# Solar_ve_r_zgar_kart.net
KiCad netlist of a schematic drawn in EAGLE
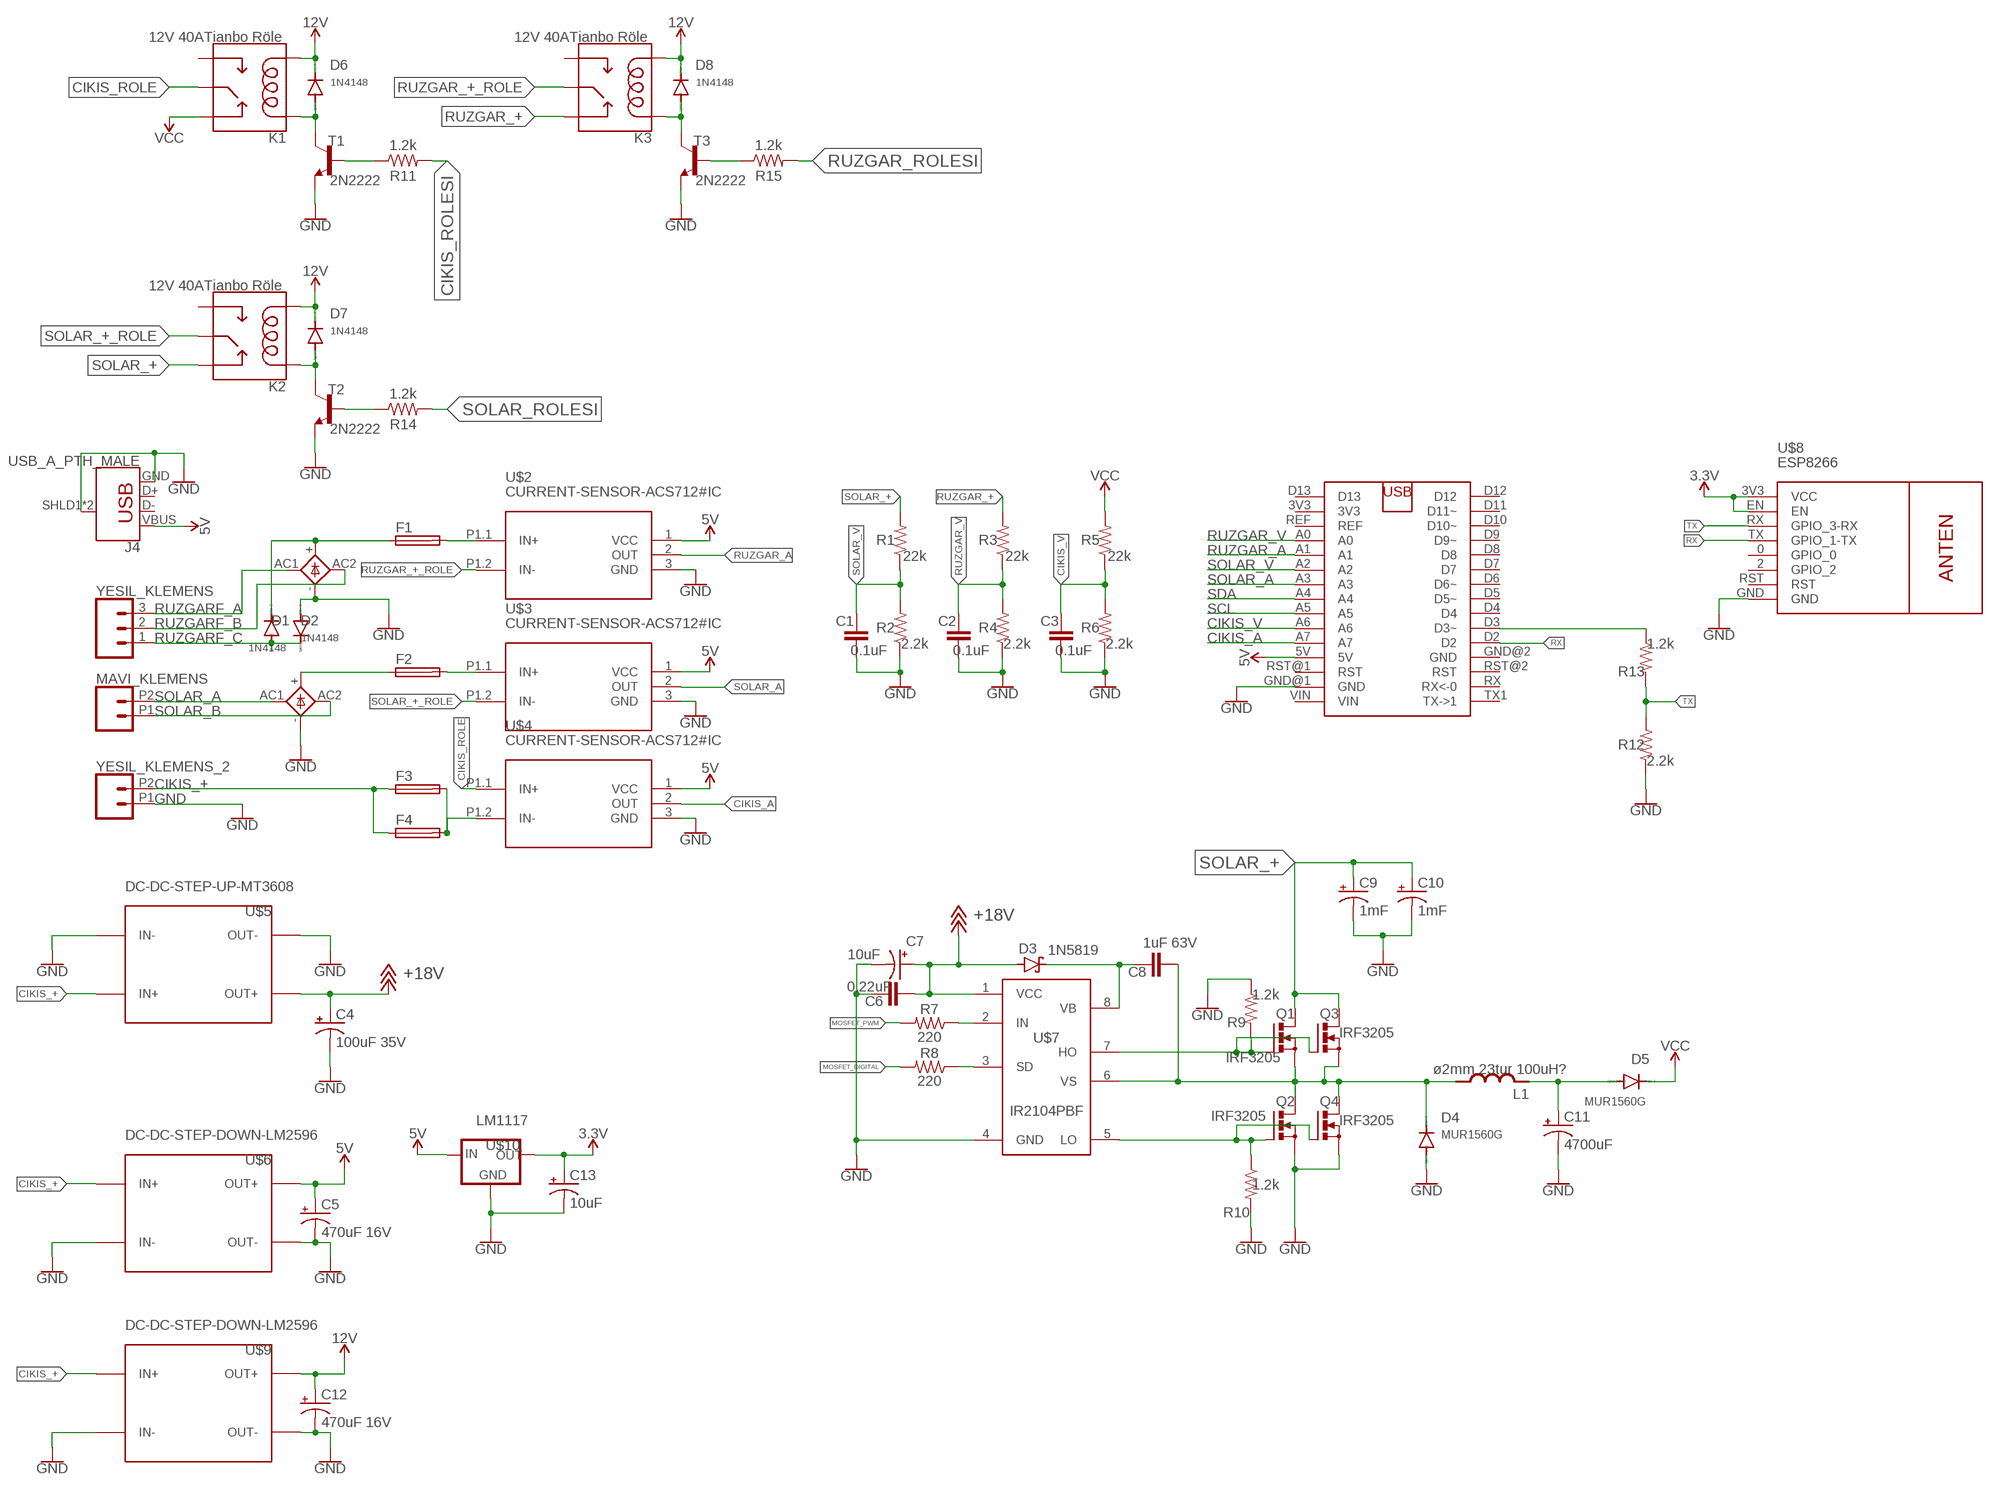
[diagram p0: schematic, sheet 1]

(export (version "E")
  (design (tool "Eeschema 10.0.6"))
  (components
    (comp (ref "B1")
      (value "FB15")
      (footprint "eagle-import:FB15")
      (libsource (lib "eagle-import") (part "FB15"))
    )
    (comp (ref "B2")
      (value "FB15")
      (footprint "eagle-import:FB15")
      (libsource (lib "eagle-import") (part "FB15"))
    )
    (comp (ref "C1")
      (value "0.1uF")
      (footprint "eagle-import:CAP-PTH-SMALL-KIT")
      (libsource (lib "eagle-import") (part "0.1UF-KIT-EZ-50V-20%"))
    )
    (comp (ref "C2")
      (value "0.1uF")
      (footprint "eagle-import:CAP-PTH-SMALL-KIT")
      (libsource (lib "eagle-import") (part "0.1UF-KIT-EZ-50V-20%"))
    )
    (comp (ref "C3")
      (value "0.1uF")
      (footprint "eagle-import:CAP-PTH-SMALL-KIT")
      (libsource (lib "eagle-import") (part "0.1UF-KIT-EZ-50V-20%"))
    )
    (comp (ref "C4")
      (value "100uF 35V")
      (footprint "eagle-import:CPOL-RADIAL-2.5MM-6.5MM")
      (libsource (lib "eagle-import") (part "100UF-POLAR-RADIAL-2.5MM-25V-20%"))
    )
    (comp (ref "C5")
      (value "470uF 16V")
      (footprint "eagle-import:CPOL-RADIAL-2.5MM-6.5MM")
      (libsource (lib "eagle-import") (part "100UF-POLAR-RADIAL-2.5MM-25V-20%"))
    )
    (comp (ref "C6")
      (value "0.22uF")
      (footprint "eagle-import:CAP-PTH-SMALL-KIT")
      (libsource (lib "eagle-import") (part "0.1UF-KIT-EZ-50V-20%"))
    )
    (comp (ref "C7")
      (value "10uF")
      (footprint "eagle-import:CPOL-RADIAL-2.5MM-5MM")
      (libsource (lib "eagle-import") (part "10UF-POLAR-RADIAL-2.5MM-25V-20%"))
    )
    (comp (ref "C8")
      (value "1uF 63V")
      (footprint "eagle-import:CAP-PTH-SMALL-KIT")
      (libsource (lib "eagle-import") (part "0.1UF-KIT-EZ-50V-20%"))
    )
    (comp (ref "C9")
      (value "1mF")
      (footprint "eagle-import:CPOL-RADIAL-5MM-10MM")
      (libsource (lib "eagle-import") (part "1000UF-RADIAL-5MM-25V-20%"))
    )
    (comp (ref "C10")
      (value "1mF")
      (footprint "eagle-import:CPOL-RADIAL-5MM-10MM")
      (libsource (lib "eagle-import") (part "1000UF-RADIAL-5MM-25V-20%"))
    )
    (comp (ref "C11")
      (value "4700uF")
      (footprint "eagle-import:CPOL-RADIAL-5MM-10MM")
      (libsource (lib "eagle-import") (part "1000UF-RADIAL-5MM-25V-20%"))
    )
    (comp (ref "C12")
      (value "470uF 16V")
      (footprint "eagle-import:CPOL-RADIAL-2.5MM-6.5MM")
      (libsource (lib "eagle-import") (part "100UF-POLAR-RADIAL-2.5MM-25V-20%"))
    )
    (comp (ref "C13")
      (value "10uF")
      (footprint "eagle-import:CPOL-RADIAL-2.5MM-5MM")
      (libsource (lib "eagle-import") (part "10UF-POLAR-RADIAL-2.5MM-25V-20%"))
    )
    (comp (ref "D1")
      (value "1N4148")
      (footprint "eagle-import:DO35-7")
      (libsource (lib "eagle-import") (part "1N4148DO35-7"))
    )
    (comp (ref "D2")
      (value "1N4148")
      (footprint "eagle-import:DO35-7")
      (libsource (lib "eagle-import") (part "1N4148DO35-7"))
    )
    (comp (ref "D3")
      (value "1N5819")
      (footprint "eagle-import:DO41-7.6")
      (libsource (lib "eagle-import") (part "1N5819-B"))
    )
    (comp (ref "D4")
      (value "MUR1560G")
      (footprint "eagle-import:TO220ACS")
      (libsource (lib "eagle-import") (part "DIODE-TO220V"))
    )
    (comp (ref "D5")
      (value "MUR1560G")
      (footprint "eagle-import:TO220ACS")
      (libsource (lib "eagle-import") (part "DIODE-TO220V"))
    )
    (comp (ref "D6")
      (value "1N4148")
      (footprint "eagle-import:DO35-7")
      (libsource (lib "eagle-import") (part "1N4148DO35-7"))
    )
    (comp (ref "D7")
      (value "1N4148")
      (footprint "eagle-import:DO35-7")
      (libsource (lib "eagle-import") (part "1N4148DO35-7"))
    )
    (comp (ref "D8")
      (value "1N4148")
      (footprint "eagle-import:DO35-7")
      (libsource (lib "eagle-import") (part "1N4148DO35-7"))
    )
    (comp (ref "F1")
      (value "19560")
      (footprint "eagle-import:19560")
      (fields (field (name "MPN") "56000001009"))
      (libsource (lib "eagle-import") (part "19560"))
    )
    (comp (ref "F2")
      (value "19560")
      (footprint "eagle-import:19560")
      (fields (field (name "MPN") "56000001009"))
      (libsource (lib "eagle-import") (part "19560"))
    )
    (comp (ref "F3")
      (value "19560")
      (footprint "eagle-import:19560")
      (fields (field (name "MPN") "56000001009"))
      (libsource (lib "eagle-import") (part "19560"))
    )
    (comp (ref "F4")
      (value "19560")
      (footprint "eagle-import:19560")
      (fields (field (name "MPN") "56000001009"))
      (libsource (lib "eagle-import") (part "19560"))
    )
    (comp (ref "J4")
      (value "USB_A_PTH_MALE")
      (footprint "eagle-import:USB-A-H")
      (libsource (lib "eagle-import") (part "USB_A_PTH_MALE"))
    )
    (comp (ref "K1")
      (value "12V 40ATianbo Röle")
      (footprint "eagle-import:RELAY-JZC")
      (libsource (lib "eagle-import") (part "RELAY-SPDT-JZC-11F"))
    )
    (comp (ref "K2")
      (value "12V 40ATianbo Röle")
      (footprint "eagle-import:RELAY-JZC")
      (libsource (lib "eagle-import") (part "RELAY-SPDT-JZC-11F"))
    )
    (comp (ref "K3")
      (value "12V 40ATianbo Röle")
      (footprint "eagle-import:RELAY-JZC")
      (libsource (lib "eagle-import") (part "RELAY-SPDT-JZC-11F"))
    )
    (comp (ref "L1")
      (value "ø2mm 23tur 100uH?")
      (footprint "eagle-import:L10-2")
      (libsource (lib "eagle-import") (part "L10-2"))
    )
    (comp (ref "MAVI_KLEMENS")
      (value "CONN_022.54MM_SCREWTERM")
      (footprint "eagle-import:1X02_2.54_SCREWTERM")
      (libsource (lib "eagle-import") (part "CONN_022.54MM_SCREWTERM"))
    )
    (comp (ref "Q1")
      (value "IRF3205")
      (footprint "eagle-import:TO220BV")
      (libsource (lib "eagle-import") (part "PMOSFET_NTO220BV"))
    )
    (comp (ref "Q2")
      (value "IRF3205")
      (footprint "eagle-import:TO220BV")
      (libsource (lib "eagle-import") (part "PMOSFET_NTO220BV"))
    )
    (comp (ref "Q3")
      (value "IRF3205")
      (footprint "eagle-import:TO220BV")
      (libsource (lib "eagle-import") (part "PMOSFET_NTO220BV"))
    )
    (comp (ref "Q4")
      (value "IRF3205")
      (footprint "eagle-import:TO220BV")
      (libsource (lib "eagle-import") (part "PMOSFET_NTO220BV"))
    )
    (comp (ref "R1")
      (value "22k")
      (footprint "eagle-import:AXIAL-0.3")
      (libsource (lib "eagle-import") (part "RESISTORAXIAL-0.3"))
    )
    (comp (ref "R2")
      (value "2.2k")
      (footprint "eagle-import:AXIAL-0.3")
      (libsource (lib "eagle-import") (part "RESISTORAXIAL-0.3"))
    )
    (comp (ref "R3")
      (value "22k")
      (footprint "eagle-import:AXIAL-0.3")
      (libsource (lib "eagle-import") (part "RESISTORAXIAL-0.3"))
    )
    (comp (ref "R4")
      (value "2.2k")
      (footprint "eagle-import:AXIAL-0.3")
      (libsource (lib "eagle-import") (part "RESISTORAXIAL-0.3"))
    )
    (comp (ref "R5")
      (value "22k")
      (footprint "eagle-import:AXIAL-0.3")
      (libsource (lib "eagle-import") (part "RESISTORAXIAL-0.3"))
    )
    (comp (ref "R6")
      (value "2.2k")
      (footprint "eagle-import:AXIAL-0.3")
      (libsource (lib "eagle-import") (part "RESISTORAXIAL-0.3"))
    )
    (comp (ref "R7")
      (value "220")
      (footprint "eagle-import:AXIAL-0.3")
      (libsource (lib "eagle-import") (part "RESISTORAXIAL-0.3"))
    )
    (comp (ref "R8")
      (value "220")
      (footprint "eagle-import:AXIAL-0.3")
      (libsource (lib "eagle-import") (part "RESISTORAXIAL-0.3"))
    )
    (comp (ref "R9")
      (value "1.2k")
      (footprint "eagle-import:AXIAL-0.3")
      (libsource (lib "eagle-import") (part "RESISTORAXIAL-0.3"))
    )
    (comp (ref "R10")
      (value "1.2k")
      (footprint "eagle-import:AXIAL-0.3")
      (libsource (lib "eagle-import") (part "RESISTORAXIAL-0.3"))
    )
    (comp (ref "R11")
      (value "1.2k")
      (footprint "eagle-import:AXIAL-0.3")
      (libsource (lib "eagle-import") (part "RESISTORAXIAL-0.3"))
    )
    (comp (ref "R12")
      (value "2.2k")
      (footprint "eagle-import:AXIAL-0.3")
      (libsource (lib "eagle-import") (part "RESISTORAXIAL-0.3"))
    )
    (comp (ref "R13")
      (value "1.2k")
      (footprint "eagle-import:AXIAL-0.3")
      (libsource (lib "eagle-import") (part "RESISTORAXIAL-0.3"))
    )
    (comp (ref "R14")
      (value "1.2k")
      (footprint "eagle-import:AXIAL-0.3")
      (libsource (lib "eagle-import") (part "RESISTORAXIAL-0.3"))
    )
    (comp (ref "R15")
      (value "1.2k")
      (footprint "eagle-import:AXIAL-0.3")
      (libsource (lib "eagle-import") (part "RESISTORAXIAL-0.3"))
    )
    (comp (ref "T1")
      (value "2N2222")
      (footprint "eagle-import:TO92-EBC")
      (libsource (lib "eagle-import") (part "-NPN-TO92-EBC2N2222"))
    )
    (comp (ref "T2")
      (value "2N2222")
      (footprint "eagle-import:TO92-EBC")
      (libsource (lib "eagle-import") (part "-NPN-TO92-EBC2N2222"))
    )
    (comp (ref "T3")
      (value "2N2222")
      (footprint "eagle-import:TO92-EBC")
      (libsource (lib "eagle-import") (part "-NPN-TO92-EBC2N2222"))
    )
    (comp (ref "U$1")
      (value "ARDUINO_NANO")
      (footprint "eagle-import:ARDUINO_NANO")
      (libsource (lib "eagle-import") (part "ARDUINO_NANO"))
    )
    (comp (ref "U$2")
      (value "CURRENT-SENSOR-ACS712#IC")
      (footprint "eagle-import:CURRENT-SENSOR-ACS712#IC")
      (libsource (lib "eagle-import") (part "CURRENT-SENSOR-ACS712#IC"))
    )
    (comp (ref "U$3")
      (value "CURRENT-SENSOR-ACS712#IC")
      (footprint "eagle-import:CURRENT-SENSOR-ACS712#IC")
      (libsource (lib "eagle-import") (part "CURRENT-SENSOR-ACS712#IC"))
    )
    (comp (ref "U$4")
      (value "CURRENT-SENSOR-ACS712#IC")
      (footprint "eagle-import:CURRENT-SENSOR-ACS712#IC")
      (libsource (lib "eagle-import") (part "CURRENT-SENSOR-ACS712#IC"))
    )
    (comp (ref "U$5")
      (value "DC-DC-STEP-UP-MT3608")
      (footprint "eagle-import:DC-DC-STEP-UP-MT3608")
      (fields (field (name "SPICEPREFIX") "E"))
      (libsource (lib "eagle-import") (part "DC-DC-STEP-UP-MT3608"))
    )
    (comp (ref "U$6")
      (value "DC-DC-STEP-DOWN-LM2596")
      (footprint "eagle-import:DC-DC-STEP-DOWN-LM2596")
      (libsource (lib "eagle-import") (part "DC-DC-STEP-DOWN-LM2596"))
    )
    (comp (ref "U$7")
      (value "IR2104PBF")
      (footprint "eagle-import:DIP-8")
      (libsource (lib "eagle-import") (part "IR2104PBF"))
    )
    (comp (ref "U$8")
      (value "ESP8266")
      (footprint "eagle-import:ESP8266")
      (libsource (lib "eagle-import") (part "ESP8266"))
    )
    (comp (ref "U$9")
      (value "DC-DC-STEP-DOWN-LM2596")
      (footprint "eagle-import:DC-DC-STEP-DOWN-LM2596")
      (libsource (lib "eagle-import") (part "DC-DC-STEP-DOWN-LM2596"))
    )
    (comp (ref "U$10")
      (value "LM1117")
      (footprint "eagle-import:TO-220")
      (libsource (lib "eagle-import") (part "LM1117"))
    )
    (comp (ref "YESIL_KLEMENS")
      (value "CONN_03-SCREW-5MM")
      (footprint "eagle-import:SCREWTERMINAL-5MM-3")
      (libsource (lib "eagle-import") (part "CONN_03-SCREW-5MM"))
    )
    (comp (ref "YESIL_KLEMENS_2")
      (value "CONN_022.54MM_SCREWTERM")
      (footprint "eagle-import:1X02_2.54_SCREWTERM")
      (libsource (lib "eagle-import") (part "CONN_022.54MM_SCREWTERM"))
    )
  )
  (nets
    (net (code "1") (name "+18V") (class "Default")
      (node (ref "C4") (pin "1") (pinfunction "+_1") (pintype "passive"))
      (node (ref "C6") (pin "2") (pinfunction "2_2") (pintype "passive"))
      (node (ref "C7") (pin "1") (pinfunction "+_1") (pintype "passive"))
      (node (ref "D3") (pin "A") (pinfunction "A_A") (pintype "passive"))
      (node (ref "U$5") (pin "OUT+") (pinfunction "OUT+_OUT+") (pintype "bidirectional"))
      (node (ref "U$7") (pin "1") (pinfunction "VCC_1") (pintype "bidirectional"))
    )
    (net (code "2") (name "/RUZGARF_A") (class "Default")
      (node (ref "B2") (pin "AC1") (pinfunction "AC1_AC1") (pintype "passive"))
      (node (ref "YESIL_KLEMENS") (pin "3") (pinfunction "3_3") (pintype "passive"))
    )
    (net (code "3") (name "/RUZGARF_B") (class "Default")
      (node (ref "B2") (pin "AC2") (pinfunction "AC2_AC2") (pintype "passive"))
      (node (ref "YESIL_KLEMENS") (pin "2") (pinfunction "2_2") (pintype "passive"))
    )
    (net (code "4") (name "/RUZGARF_C") (class "Default")
      (node (ref "D1") (pin "A") (pinfunction "A_A") (pintype "passive"))
      (node (ref "D2") (pin "C") (pinfunction "C_C") (pintype "passive"))
      (node (ref "YESIL_KLEMENS") (pin "1") (pinfunction "1_1") (pintype "passive"))
    )
    (net (code "5") (name "/SCL") (class "Default")
      (node (ref "U$1") (pin "A5") (pinfunction "A5_A5") (pintype "bidirectional"))
    )
    (net (code "6") (name "/SDA") (class "Default")
      (node (ref "U$1") (pin "A4") (pinfunction "A4_A4") (pintype "bidirectional"))
    )
    (net (code "7") (name "/SOLAR_B") (class "Default")
      (node (ref "B1") (pin "AC2") (pinfunction "AC2_AC2") (pintype "passive"))
      (node (ref "MAVI_KLEMENS") (pin "P1") (pinfunction "1_P1") (pintype "passive"))
    )
    (net (code "8") (name "3.3V") (class "Default")
      (node (ref "C13") (pin "1") (pinfunction "+_1") (pintype "passive"))
      (node (ref "U$10") (pin "2") (pinfunction "OUT_2") (pintype "output"))
      (node (ref "U$8") (pin "3V3") (pinfunction "VCC_3V3") (pintype "power_in"))
      (node (ref "U$8") (pin "EN") (pinfunction "EN_EN") (pintype "bidirectional"))
    )
    (net (code "9") (name "5V") (class "Default")
      (node (ref "C5") (pin "1") (pinfunction "+_1") (pintype "passive"))
      (node (ref "J4") (pin "VBUS") (pinfunction "VBUS_VBUS") (pintype "power_in"))
      (node (ref "U$1") (pin "5V") (pinfunction "5V_5V") (pintype "bidirectional"))
      (node (ref "U$10") (pin "3") (pinfunction "IN_3") (pintype "input"))
      (node (ref "U$2") (pin "1") (pinfunction "VCC_1") (pintype "power_in"))
      (node (ref "U$3") (pin "1") (pinfunction "VCC_1") (pintype "power_in"))
      (node (ref "U$4") (pin "1") (pinfunction "VCC_1") (pintype "power_in"))
      (node (ref "U$6") (pin "OUT+") (pinfunction "OUT+_OUT+") (pintype "bidirectional"))
    )
    (net (code "10") (name "12V") (class "Default")
      (node (ref "C12") (pin "1") (pinfunction "+_1") (pintype "passive"))
      (node (ref "D6") (pin "C") (pinfunction "C_C") (pintype "passive"))
      (node (ref "D7") (pin "C") (pinfunction "C_C") (pintype "passive"))
      (node (ref "D8") (pin "C") (pinfunction "C_C") (pintype "passive"))
      (node (ref "K1") (pin "1") (pinfunction "COIL2_1") (pintype "bidirectional"))
      (node (ref "K2") (pin "1") (pinfunction "COIL2_1") (pintype "bidirectional"))
      (node (ref "K3") (pin "1") (pinfunction "COIL2_1") (pintype "bidirectional"))
      (node (ref "U$9") (pin "OUT+") (pinfunction "OUT+_OUT+") (pintype "bidirectional"))
    )
    (net (code "11") (name "CIKIS_+") (class "Default")
      (node (ref "F3") (pin "1") (pinfunction "1_1") (pintype "passive"))
      (node (ref "F4") (pin "1") (pinfunction "1_1") (pintype "passive"))
      (node (ref "U$5") (pin "IN+") (pinfunction "IN+_IN+") (pintype "bidirectional"))
      (node (ref "U$6") (pin "IN+") (pinfunction "IN+_IN+") (pintype "bidirectional"))
      (node (ref "U$9") (pin "IN+") (pinfunction "IN+_IN+") (pintype "bidirectional"))
      (node (ref "YESIL_KLEMENS_2") (pin "P2") (pinfunction "2_P2") (pintype "passive"))
    )
    (net (code "12") (name "CIKIS_A") (class "Default")
      (node (ref "U$1") (pin "A7") (pinfunction "A7_A7") (pintype "bidirectional"))
      (node (ref "U$4") (pin "2") (pinfunction "OUT_2") (pintype "output"))
    )
    (net (code "13") (name "CIKIS_ROLE") (class "Default")
      (node (ref "K1") (pin "4") (pinfunction "MAIN_4") (pintype "bidirectional"))
      (node (ref "U$4") (pin "P1.1") (pinfunction "IN+_P1.1") (pintype "bidirectional"))
    )
    (net (code "14") (name "CIKIS_ROLESI") (class "Default")
      (node (ref "R11") (pin "P$2") (pinfunction "2_P$2") (pintype "passive"))
    )
    (net (code "15") (name "CIKIS_V") (class "Default")
      (node (ref "C3") (pin "1") (pinfunction "1_1") (pintype "passive"))
      (node (ref "R5") (pin "P$1") (pinfunction "1_P$1") (pintype "passive"))
      (node (ref "R6") (pin "P$2") (pinfunction "2_P$2") (pintype "passive"))
      (node (ref "U$1") (pin "A6") (pinfunction "A6_A6") (pintype "bidirectional"))
    )
    (net (code "16") (name "GND") (class "Default")
      (node (ref "B1") (pin "-") (pinfunction "-_-") (pintype "passive"))
      (node (ref "B2") (pin "-") (pinfunction "-_-") (pintype "passive"))
      (node (ref "C1") (pin "2") (pinfunction "2_2") (pintype "passive"))
      (node (ref "C10") (pin "-") (pinfunction "-_-") (pintype "passive"))
      (node (ref "C11") (pin "-") (pinfunction "-_-") (pintype "passive"))
      (node (ref "C12") (pin "2") (pinfunction "-_2") (pintype "passive"))
      (node (ref "C13") (pin "2") (pinfunction "-_2") (pintype "passive"))
      (node (ref "C2") (pin "2") (pinfunction "2_2") (pintype "passive"))
      (node (ref "C3") (pin "2") (pinfunction "2_2") (pintype "passive"))
      (node (ref "C4") (pin "2") (pinfunction "-_2") (pintype "passive"))
      (node (ref "C5") (pin "2") (pinfunction "-_2") (pintype "passive"))
      (node (ref "C6") (pin "1") (pinfunction "1_1") (pintype "passive"))
      (node (ref "C7") (pin "2") (pinfunction "-_2") (pintype "passive"))
      (node (ref "C9") (pin "-") (pinfunction "-_-") (pintype "passive"))
      (node (ref "D2") (pin "A") (pinfunction "A_A") (pintype "passive"))
      (node (ref "D4") (pin "A") (pinfunction "A_A") (pintype "passive"))
      (node (ref "J4") (pin "GND") (pinfunction "GND_GND") (pintype "power_in"))
      (node (ref "J4") (pin "SHLD1") (pinfunction "SHIELD_SHLD1") (pintype "bidirectional"))
      (node (ref "J4") (pin "SHLD2") (pinfunction "SHIELD_SHLD2") (pintype "bidirectional"))
      (node (ref "Q2") (pin "S") (pinfunction "S_S") (pintype "passive"))
      (node (ref "Q4") (pin "S") (pinfunction "S_S") (pintype "passive"))
      (node (ref "R10") (pin "P$2") (pinfunction "2_P$2") (pintype "passive"))
      (node (ref "R12") (pin "P$1") (pinfunction "1_P$1") (pintype "passive"))
      (node (ref "R2") (pin "P$1") (pinfunction "1_P$1") (pintype "passive"))
      (node (ref "R4") (pin "P$1") (pinfunction "1_P$1") (pintype "passive"))
      (node (ref "R6") (pin "P$1") (pinfunction "1_P$1") (pintype "passive"))
      (node (ref "R9") (pin "P$1") (pinfunction "1_P$1") (pintype "passive"))
      (node (ref "T1") (pin "E") (pinfunction "E_E") (pintype "passive"))
      (node (ref "T2") (pin "E") (pinfunction "E_E") (pintype "passive"))
      (node (ref "T3") (pin "E") (pinfunction "E_E") (pintype "passive"))
      (node (ref "U$1") (pin "GND@1") (pinfunction "GND_GND@1") (pintype "bidirectional"))
      (node (ref "U$10") (pin "1") (pinfunction "GND_1") (pintype "input"))
      (node (ref "U$2") (pin "3") (pinfunction "GND_3") (pintype "power_in"))
      (node (ref "U$3") (pin "3") (pinfunction "GND_3") (pintype "power_in"))
      (node (ref "U$4") (pin "3") (pinfunction "GND_3") (pintype "power_in"))
      (node (ref "U$5") (pin "IN-") (pinfunction "IN-_IN-") (pintype "bidirectional"))
      (node (ref "U$5") (pin "OUT-") (pinfunction "OUT-_OUT-") (pintype "bidirectional"))
      (node (ref "U$6") (pin "IN-") (pinfunction "IN-_IN-") (pintype "bidirectional"))
      (node (ref "U$6") (pin "OUT-") (pinfunction "OUT-_OUT-") (pintype "bidirectional"))
      (node (ref "U$7") (pin "4") (pinfunction "GND_4") (pintype "bidirectional"))
      (node (ref "U$8") (pin "GND") (pinfunction "GND_GND") (pintype "power_in"))
      (node (ref "U$9") (pin "IN-") (pinfunction "IN-_IN-") (pintype "bidirectional"))
      (node (ref "U$9") (pin "OUT-") (pinfunction "OUT-_OUT-") (pintype "bidirectional"))
      (node (ref "YESIL_KLEMENS_2") (pin "P1") (pinfunction "1_P1") (pintype "passive"))
    )
    (net (code "17") (name "MOSFET_DIGITAL") (class "Default")
      (node (ref "R8") (pin "P$2") (pinfunction "2_P$2") (pintype "passive"))
    )
    (net (code "18") (name "MOSFET_PWM") (class "Default")
      (node (ref "R7") (pin "P$2") (pinfunction "2_P$2") (pintype "passive"))
    )
    (net (code "19") (name "Net-(B1-Pad+)") (class "Default")
      (node (ref "B1") (pin "+") (pinfunction "+_+") (pintype "passive"))
      (node (ref "F2") (pin "1") (pinfunction "1_1") (pintype "passive"))
    )
    (net (code "20") (name "Net-(B2-Pad+)") (class "Default")
      (node (ref "B2") (pin "+") (pinfunction "+_+") (pintype "passive"))
      (node (ref "D1") (pin "C") (pinfunction "C_C") (pintype "passive"))
      (node (ref "F1") (pin "1") (pinfunction "1_1") (pintype "passive"))
    )
    (net (code "21") (name "Net-(C11-Pad+)") (class "Default")
      (node (ref "C11") (pin "+") (pinfunction "+_+") (pintype "passive"))
      (node (ref "D5") (pin "A") (pinfunction "A_A") (pintype "passive"))
      (node (ref "L1") (pin "P$3") (pinfunction "2_P$3") (pintype "passive"))
      (node (ref "L1") (pin "P$4") (pinfunction "2_P$4") (pintype "passive"))
    )
    (net (code "22") (name "Net-(K1-COIL1)") (class "Default")
      (node (ref "D6") (pin "A") (pinfunction "A_A") (pintype "passive"))
      (node (ref "K1") (pin "5") (pinfunction "COIL1_5") (pintype "bidirectional"))
      (node (ref "T1") (pin "C") (pinfunction "C_C") (pintype "passive"))
    )
    (net (code "23") (name "Net-(K2-COIL1)") (class "Default")
      (node (ref "D7") (pin "A") (pinfunction "A_A") (pintype "passive"))
      (node (ref "K2") (pin "5") (pinfunction "COIL1_5") (pintype "bidirectional"))
      (node (ref "T2") (pin "C") (pinfunction "C_C") (pintype "passive"))
    )
    (net (code "24") (name "Net-(K3-COIL1)") (class "Default")
      (node (ref "D8") (pin "A") (pinfunction "A_A") (pintype "passive"))
      (node (ref "K3") (pin "5") (pinfunction "COIL1_5") (pintype "bidirectional"))
      (node (ref "T3") (pin "C") (pinfunction "C_C") (pintype "passive"))
    )
    (net (code "25") (name "Net-(R7-1)") (class "Default")
      (node (ref "R7") (pin "P$1") (pinfunction "1_P$1") (pintype "passive"))
      (node (ref "U$7") (pin "2") (pinfunction "IN_2") (pintype "bidirectional"))
    )
    (net (code "26") (name "Net-(R8-1)") (class "Default")
      (node (ref "R8") (pin "P$1") (pinfunction "1_P$1") (pintype "passive"))
      (node (ref "U$7") (pin "3") (pinfunction "SD_3") (pintype "bidirectional"))
    )
    (net (code "27") (name "Net-(R9-2)") (class "Default")
      (node (ref "Q1") (pin "G") (pinfunction "G_G") (pintype "passive"))
      (node (ref "Q3") (pin "G") (pinfunction "G_G") (pintype "passive"))
      (node (ref "R9") (pin "P$2") (pinfunction "2_P$2") (pintype "passive"))
      (node (ref "U$7") (pin "7") (pinfunction "HO_7") (pintype "bidirectional"))
    )
    (net (code "28") (name "Net-(R10-1)") (class "Default")
      (node (ref "Q2") (pin "G") (pinfunction "G_G") (pintype "passive"))
      (node (ref "Q4") (pin "G") (pinfunction "G_G") (pintype "passive"))
      (node (ref "R10") (pin "P$1") (pinfunction "1_P$1") (pintype "passive"))
      (node (ref "U$7") (pin "5") (pinfunction "LO_5") (pintype "bidirectional"))
    )
    (net (code "29") (name "Net-(R11-1)") (class "Default")
      (node (ref "R11") (pin "P$1") (pinfunction "1_P$1") (pintype "passive"))
      (node (ref "T1") (pin "B") (pinfunction "B_B") (pintype "passive"))
    )
    (net (code "30") (name "Net-(R13-1)") (class "Default")
      (node (ref "R13") (pin "P$1") (pinfunction "1_P$1") (pintype "passive"))
      (node (ref "U$1") (pin "D3") (pinfunction "D3~{}_D3") (pintype "bidirectional"))
    )
    (net (code "31") (name "Net-(R14-1)") (class "Default")
      (node (ref "R14") (pin "P$1") (pinfunction "1_P$1") (pintype "passive"))
      (node (ref "T2") (pin "B") (pinfunction "B_B") (pintype "passive"))
    )
    (net (code "32") (name "Net-(R15-1)") (class "Default")
      (node (ref "R15") (pin "P$1") (pinfunction "1_P$1") (pintype "passive"))
      (node (ref "T3") (pin "B") (pinfunction "B_B") (pintype "passive"))
    )
    (net (code "33") (name "Net-(U$2-IN+)") (class "Default")
      (node (ref "F1") (pin "2") (pinfunction "2_2") (pintype "passive"))
      (node (ref "U$2") (pin "P1.1") (pinfunction "IN+_P1.1") (pintype "bidirectional"))
    )
    (net (code "34") (name "Net-(U$3-IN+)") (class "Default")
      (node (ref "F2") (pin "2") (pinfunction "2_2") (pintype "passive"))
      (node (ref "U$3") (pin "P1.1") (pinfunction "IN+_P1.1") (pintype "bidirectional"))
    )
    (net (code "35") (name "Net-(U$4-IN-)") (class "Default")
      (node (ref "F3") (pin "2") (pinfunction "2_2") (pintype "passive"))
      (node (ref "F4") (pin "2") (pinfunction "2_2") (pintype "passive"))
      (node (ref "U$4") (pin "P1.2") (pinfunction "IN-_P1.2") (pintype "bidirectional"))
    )
    (net (code "36") (name "Net-(U$7-VB)") (class "Default")
      (node (ref "C8") (pin "1") (pinfunction "1_1") (pintype "passive"))
      (node (ref "D3") (pin "C") (pinfunction "C_C") (pintype "passive"))
      (node (ref "U$7") (pin "8") (pinfunction "VB_8") (pintype "bidirectional"))
    )
    (net (code "37") (name "Net-(U$7-VS)") (class "Default")
      (node (ref "C8") (pin "2") (pinfunction "2_2") (pintype "passive"))
      (node (ref "D4") (pin "C") (pinfunction "C_C") (pintype "passive"))
      (node (ref "L1") (pin "P$1") (pinfunction "1_P$1") (pintype "passive"))
      (node (ref "L1") (pin "P$2") (pinfunction "1_P$2") (pintype "passive"))
      (node (ref "Q1") (pin "S") (pinfunction "S_S") (pintype "passive"))
      (node (ref "Q2") (pin "D") (pinfunction "D_D") (pintype "passive"))
      (node (ref "Q3") (pin "S") (pinfunction "S_S") (pintype "passive"))
      (node (ref "Q4") (pin "D") (pinfunction "D_D") (pintype "passive"))
      (node (ref "U$7") (pin "6") (pinfunction "VS_6") (pintype "bidirectional"))
    )
    (net (code "38") (name "RUZGAR_+") (class "Default")
      (node (ref "K3") (pin "2") (pinfunction "NC_2") (pintype "bidirectional"))
      (node (ref "R3") (pin "P$2") (pinfunction "2_P$2") (pintype "passive"))
    )
    (net (code "39") (name "RUZGAR_+_ROLE") (class "Default")
      (node (ref "K3") (pin "4") (pinfunction "MAIN_4") (pintype "bidirectional"))
      (node (ref "U$2") (pin "P1.2") (pinfunction "IN-_P1.2") (pintype "bidirectional"))
    )
    (net (code "40") (name "RUZGAR_A") (class "Default")
      (node (ref "U$1") (pin "A1") (pinfunction "A1_A1") (pintype "bidirectional"))
      (node (ref "U$2") (pin "2") (pinfunction "OUT_2") (pintype "output"))
    )
    (net (code "41") (name "RUZGAR_ROLESI") (class "Default")
      (node (ref "R15") (pin "P$2") (pinfunction "2_P$2") (pintype "passive"))
    )
    (net (code "42") (name "RUZGAR_V") (class "Default")
      (node (ref "C2") (pin "1") (pinfunction "1_1") (pintype "passive"))
      (node (ref "R3") (pin "P$1") (pinfunction "1_P$1") (pintype "passive"))
      (node (ref "R4") (pin "P$2") (pinfunction "2_P$2") (pintype "passive"))
      (node (ref "U$1") (pin "A0") (pinfunction "A0_A0") (pintype "bidirectional"))
    )
    (net (code "43") (name "RX") (class "Default")
      (node (ref "U$1") (pin "D2") (pinfunction "D2_D2") (pintype "bidirectional"))
      (node (ref "U$8") (pin "TX") (pinfunction "GPIO_1-TX_TX") (pintype "bidirectional"))
    )
    (net (code "44") (name "SOLAR_+") (class "Default")
      (node (ref "C10") (pin "+") (pinfunction "+_+") (pintype "passive"))
      (node (ref "C9") (pin "+") (pinfunction "+_+") (pintype "passive"))
      (node (ref "K2") (pin "2") (pinfunction "NC_2") (pintype "bidirectional"))
      (node (ref "Q1") (pin "D") (pinfunction "D_D") (pintype "passive"))
      (node (ref "Q3") (pin "D") (pinfunction "D_D") (pintype "passive"))
      (node (ref "R1") (pin "P$2") (pinfunction "2_P$2") (pintype "passive"))
    )
    (net (code "45") (name "SOLAR_+_ROLE") (class "Default")
      (node (ref "K2") (pin "4") (pinfunction "MAIN_4") (pintype "bidirectional"))
      (node (ref "U$3") (pin "P1.2") (pinfunction "IN-_P1.2") (pintype "bidirectional"))
    )
    (net (code "46") (name "SOLAR_A") (class "Default")
      (node (ref "B1") (pin "AC1") (pinfunction "AC1_AC1") (pintype "passive"))
      (node (ref "MAVI_KLEMENS") (pin "P2") (pinfunction "2_P2") (pintype "passive"))
      (node (ref "U$1") (pin "A3") (pinfunction "A3_A3") (pintype "bidirectional"))
      (node (ref "U$3") (pin "2") (pinfunction "OUT_2") (pintype "output"))
    )
    (net (code "47") (name "SOLAR_ROLESI") (class "Default")
      (node (ref "R14") (pin "P$2") (pinfunction "2_P$2") (pintype "passive"))
    )
    (net (code "48") (name "SOLAR_V") (class "Default")
      (node (ref "C1") (pin "1") (pinfunction "1_1") (pintype "passive"))
      (node (ref "R1") (pin "P$1") (pinfunction "1_P$1") (pintype "passive"))
      (node (ref "R2") (pin "P$2") (pinfunction "2_P$2") (pintype "passive"))
      (node (ref "U$1") (pin "A2") (pinfunction "A2_A2") (pintype "bidirectional"))
    )
    (net (code "49") (name "TX") (class "Default")
      (node (ref "R12") (pin "P$2") (pinfunction "2_P$2") (pintype "passive"))
      (node (ref "R13") (pin "P$2") (pinfunction "2_P$2") (pintype "passive"))
      (node (ref "U$8") (pin "RX") (pinfunction "GPIO_3-RX_RX") (pintype "bidirectional"))
    )
    (net (code "50") (name "VCC") (class "Default")
      (node (ref "D5") (pin "C") (pinfunction "C_C") (pintype "passive"))
      (node (ref "K1") (pin "2") (pinfunction "NC_2") (pintype "bidirectional"))
      (node (ref "R5") (pin "P$2") (pinfunction "2_P$2") (pintype "passive"))
    )
    (net (code "51") (name "unconnected-(J4-PadD+)") (class "Default")
      (node (ref "J4") (pin "D+") (pinfunction "D+_D+") (pintype "bidirectional"))
    )
    (net (code "52") (name "unconnected-(J4-PadD-)") (class "Default")
      (node (ref "J4") (pin "D-") (pinfunction "D-_D-") (pintype "bidirectional"))
    )
    (net (code "53") (name "unconnected-(K1-NO-Pad3)") (class "Default")
      (node (ref "K1") (pin "3") (pinfunction "NO_3") (pintype "bidirectional"))
    )
    (net (code "54") (name "unconnected-(K2-NO-Pad3)") (class "Default")
      (node (ref "K2") (pin "3") (pinfunction "NO_3") (pintype "bidirectional"))
    )
    (net (code "55") (name "unconnected-(K3-NO-Pad3)") (class "Default")
      (node (ref "K3") (pin "3") (pinfunction "NO_3") (pintype "bidirectional"))
    )
    (net (code "56") (name "unconnected-(U$1-D5~{}-PadD5)") (class "Default")
      (node (ref "U$1") (pin "D5") (pinfunction "D5~{}_D5") (pintype "bidirectional"))
    )
    (net (code "57") (name "unconnected-(U$1-D6~{}-PadD6)") (class "Default")
      (node (ref "U$1") (pin "D6") (pinfunction "D6~{}_D6") (pintype "bidirectional"))
    )
    (net (code "58") (name "unconnected-(U$1-D9~{}-PadD9)") (class "Default")
      (node (ref "U$1") (pin "D9") (pinfunction "D9~{}_D9") (pintype "bidirectional"))
    )
    (net (code "59") (name "unconnected-(U$1-D10~{}-PadD10)") (class "Default")
      (node (ref "U$1") (pin "D10") (pinfunction "D10~{}_D10") (pintype "bidirectional"))
    )
    (net (code "60") (name "unconnected-(U$1-D11~{}-PadD11)") (class "Default")
      (node (ref "U$1") (pin "D11") (pinfunction "D11~{}_D11") (pintype "bidirectional"))
    )
    (net (code "61") (name "unconnected-(U$1-GND-PadGND@2)") (class "Default")
      (node (ref "U$1") (pin "GND@2") (pinfunction "GND_GND@2") (pintype "bidirectional"))
    )
    (net (code "62") (name "unconnected-(U$1-Pad3V3)") (class "Default")
      (node (ref "U$1") (pin "3V3") (pinfunction "3V3_3V3") (pintype "bidirectional"))
    )
    (net (code "63") (name "unconnected-(U$1-PadD4)") (class "Default")
      (node (ref "U$1") (pin "D4") (pinfunction "D4_D4") (pintype "bidirectional"))
    )
    (net (code "64") (name "unconnected-(U$1-PadD7)") (class "Default")
      (node (ref "U$1") (pin "D7") (pinfunction "D7_D7") (pintype "bidirectional"))
    )
    (net (code "65") (name "unconnected-(U$1-PadD8)") (class "Default")
      (node (ref "U$1") (pin "D8") (pinfunction "D8_D8") (pintype "bidirectional"))
    )
    (net (code "66") (name "unconnected-(U$1-PadD12)") (class "Default")
      (node (ref "U$1") (pin "D12") (pinfunction "D12_D12") (pintype "bidirectional"))
    )
    (net (code "67") (name "unconnected-(U$1-PadD13)") (class "Default")
      (node (ref "U$1") (pin "D13") (pinfunction "D13_D13") (pintype "bidirectional"))
    )
    (net (code "68") (name "unconnected-(U$1-PadREF)") (class "Default")
      (node (ref "U$1") (pin "REF") (pinfunction "REF_REF") (pintype "bidirectional"))
    )
    (net (code "69") (name "unconnected-(U$1-PadVIN)") (class "Default")
      (node (ref "U$1") (pin "VIN") (pinfunction "VIN_VIN") (pintype "bidirectional"))
    )
    (net (code "70") (name "unconnected-(U$1-RST-PadRST@1)") (class "Default")
      (node (ref "U$1") (pin "RST@1") (pinfunction "RST_RST@1") (pintype "bidirectional"))
    )
    (net (code "71") (name "unconnected-(U$1-RST-PadRST@2)") (class "Default")
      (node (ref "U$1") (pin "RST@2") (pinfunction "RST_RST@2") (pintype "bidirectional"))
    )
    (net (code "72") (name "unconnected-(U$1-RX<-0-PadRX)") (class "Default")
      (node (ref "U$1") (pin "RX") (pinfunction "RX<-0_RX") (pintype "bidirectional"))
    )
    (net (code "73") (name "unconnected-(U$1-TX->1-PadTX1)") (class "Default")
      (node (ref "U$1") (pin "TX1") (pinfunction "TX->1_TX1") (pintype "bidirectional"))
    )
    (net (code "74") (name "unconnected-(U$8-GPIO_0-Pad0)") (class "Default")
      (node (ref "U$8") (pin "0") (pinfunction "GPIO_0_0") (pintype "bidirectional"))
    )
    (net (code "75") (name "unconnected-(U$8-GPIO_2-Pad2)") (class "Default")
      (node (ref "U$8") (pin "2") (pinfunction "GPIO_2_2") (pintype "bidirectional"))
    )
    (net (code "76") (name "unconnected-(U$8-PadRST)") (class "Default")
      (node (ref "U$8") (pin "RST") (pinfunction "RST_RST") (pintype "bidirectional"))
    )
  )
)
